# bankswitch-reg.net
KiCad netlist of a schematic drawn in EAGLE
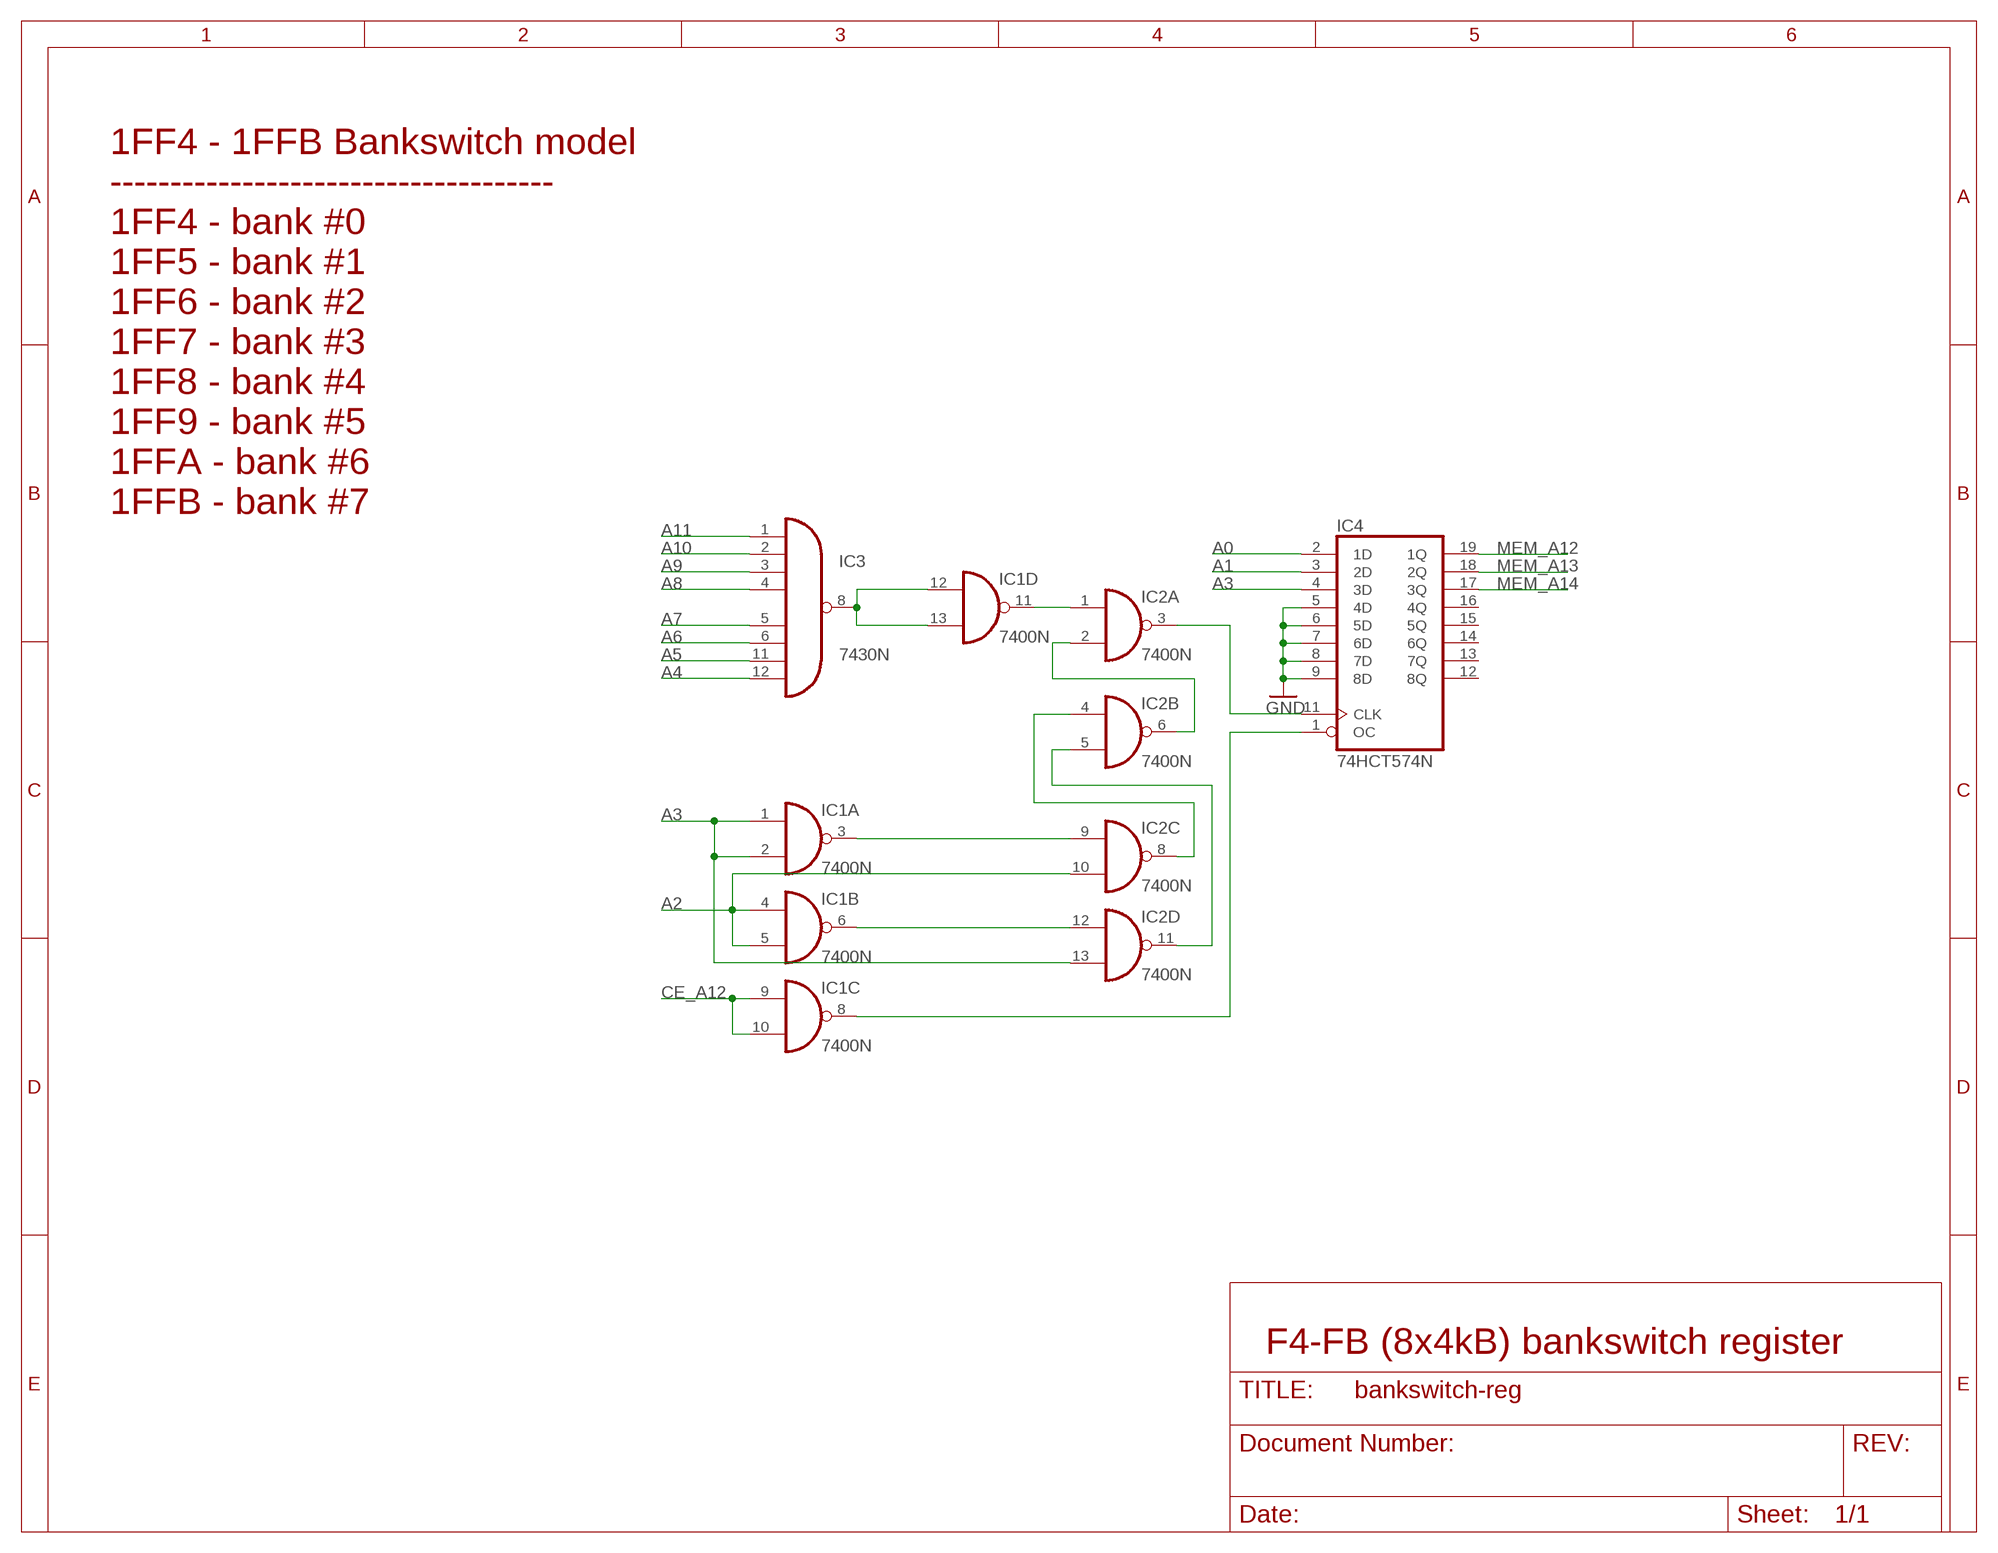
[diagram p0: schematic, sheet 1]

(export (version "E")
  (design (tool "Eeschema 10.0.6"))
  (components
    (comp (ref "IC1")
      (value "7400N")
      (footprint "eagle-import:DIL14")
      (libsource (lib "eagle-import") (part "7400N"))
    )
    (comp (ref "IC2")
      (value "7400N")
      (footprint "eagle-import:DIL14")
      (libsource (lib "eagle-import") (part "7400N"))
    )
    (comp (ref "IC3")
      (value "7430N")
      (footprint "eagle-import:DIL14")
      (libsource (lib "eagle-import") (part "7430N"))
    )
    (comp (ref "IC4")
      (value "74HCT574N")
      (footprint "eagle-import:DIL20")
      (libsource (lib "eagle-import") (part "74574NHCT"))
    )
  )
  (nets
    (net (code "1") (name "/A0") (class "Default")
      (node (ref "IC4") (pin "2") (pinfunction "1D_2") (pintype "input"))
    )
    (net (code "2") (name "/A1") (class "Default")
      (node (ref "IC4") (pin "3") (pinfunction "2D_3") (pintype "input"))
    )
    (net (code "3") (name "/A2") (class "Default")
      (node (ref "IC1") (pin "4") (pinfunction "I0_4") (pintype "input"))
      (node (ref "IC1") (pin "5") (pinfunction "I1_5") (pintype "input"))
      (node (ref "IC2") (pin "10") (pinfunction "I1_10") (pintype "input"))
    )
    (net (code "4") (name "/A3") (class "Default")
      (node (ref "IC1") (pin "1") (pinfunction "I0_1") (pintype "input"))
      (node (ref "IC1") (pin "2") (pinfunction "I1_2") (pintype "input"))
      (node (ref "IC2") (pin "13") (pinfunction "I1_13") (pintype "input"))
      (node (ref "IC4") (pin "4") (pinfunction "3D_4") (pintype "input"))
    )
    (net (code "5") (name "/A4") (class "Default")
      (node (ref "IC3") (pin "12") (pinfunction "I7_12") (pintype "input"))
    )
    (net (code "6") (name "/A5") (class "Default")
      (node (ref "IC3") (pin "11") (pinfunction "I6_11") (pintype "input"))
    )
    (net (code "7") (name "/A6") (class "Default")
      (node (ref "IC3") (pin "6") (pinfunction "I5_6") (pintype "input"))
    )
    (net (code "8") (name "/A7") (class "Default")
      (node (ref "IC3") (pin "5") (pinfunction "I4_5") (pintype "input"))
    )
    (net (code "9") (name "/A8") (class "Default")
      (node (ref "IC3") (pin "4") (pinfunction "I3_4") (pintype "input"))
    )
    (net (code "10") (name "/A9") (class "Default")
      (node (ref "IC3") (pin "3") (pinfunction "I2_3") (pintype "input"))
    )
    (net (code "11") (name "/A10") (class "Default")
      (node (ref "IC3") (pin "2") (pinfunction "I1_2") (pintype "input"))
    )
    (net (code "12") (name "/A11") (class "Default")
      (node (ref "IC3") (pin "1") (pinfunction "I0_1") (pintype "input"))
    )
    (net (code "13") (name "/CE_A12") (class "Default")
      (node (ref "IC1") (pin "10") (pinfunction "I1_10") (pintype "input"))
      (node (ref "IC1") (pin "9") (pinfunction "I0_9") (pintype "input"))
    )
    (net (code "14") (name "/MEM_A12") (class "Default")
      (node (ref "IC4") (pin "19") (pinfunction "1Q_19") (pintype "tri_state"))
    )
    (net (code "15") (name "/MEM_A13") (class "Default")
      (node (ref "IC4") (pin "18") (pinfunction "2Q_18") (pintype "tri_state"))
    )
    (net (code "16") (name "/MEM_A14") (class "Default")
      (node (ref "IC4") (pin "17") (pinfunction "3Q_17") (pintype "tri_state"))
    )
    (net (code "17") (name "GND") (class "Default")
      (node (ref "IC4") (pin "5") (pinfunction "4D_5") (pintype "input"))
      (node (ref "IC4") (pin "6") (pinfunction "5D_6") (pintype "input"))
      (node (ref "IC4") (pin "7") (pinfunction "6D_7") (pintype "input"))
      (node (ref "IC4") (pin "8") (pinfunction "7D_8") (pintype "input"))
      (node (ref "IC4") (pin "9") (pinfunction "8D_9") (pintype "input"))
    )
    (net (code "18") (name "Net-(IC1A-O)") (class "Default")
      (node (ref "IC1") (pin "3") (pinfunction "O_3") (pintype "output"))
      (node (ref "IC2") (pin "9") (pinfunction "I0_9") (pintype "input"))
    )
    (net (code "19") (name "Net-(IC1B-O)") (class "Default")
      (node (ref "IC1") (pin "6") (pinfunction "O_6") (pintype "output"))
      (node (ref "IC2") (pin "12") (pinfunction "I0_12") (pintype "input"))
    )
    (net (code "20") (name "Net-(IC1C-O)") (class "Default")
      (node (ref "IC1") (pin "8") (pinfunction "O_8") (pintype "output"))
      (node (ref "IC4") (pin "1") (pinfunction "OC_1") (pintype "input"))
    )
    (net (code "21") (name "Net-(IC1D-I0)") (class "Default")
      (node (ref "IC1") (pin "12") (pinfunction "I0_12") (pintype "input"))
      (node (ref "IC1") (pin "13") (pinfunction "I1_13") (pintype "input"))
      (node (ref "IC3") (pin "8") (pinfunction "O_8") (pintype "output"))
    )
    (net (code "22") (name "Net-(IC1D-O)") (class "Default")
      (node (ref "IC1") (pin "11") (pinfunction "O_11") (pintype "output"))
      (node (ref "IC2") (pin "1") (pinfunction "I0_1") (pintype "input"))
    )
    (net (code "23") (name "Net-(IC2A-I1)") (class "Default")
      (node (ref "IC2") (pin "2") (pinfunction "I1_2") (pintype "input"))
      (node (ref "IC2") (pin "6") (pinfunction "O_6") (pintype "output"))
    )
    (net (code "24") (name "Net-(IC2A-O)") (class "Default")
      (node (ref "IC2") (pin "3") (pinfunction "O_3") (pintype "output"))
      (node (ref "IC4") (pin "11") (pinfunction "CLK_11") (pintype "input"))
    )
    (net (code "25") (name "Net-(IC2B-I0)") (class "Default")
      (node (ref "IC2") (pin "4") (pinfunction "I0_4") (pintype "input"))
      (node (ref "IC2") (pin "8") (pinfunction "O_8") (pintype "output"))
    )
    (net (code "26") (name "Net-(IC2B-I1)") (class "Default")
      (node (ref "IC2") (pin "11") (pinfunction "O_11") (pintype "output"))
      (node (ref "IC2") (pin "5") (pinfunction "I1_5") (pintype "input"))
    )
    (net (code "27") (name "unconnected-(IC4A-4Q-Pad16)") (class "Default")
      (node (ref "IC4") (pin "16") (pinfunction "4Q_16") (pintype "tri_state"))
    )
    (net (code "28") (name "unconnected-(IC4A-5Q-Pad15)") (class "Default")
      (node (ref "IC4") (pin "15") (pinfunction "5Q_15") (pintype "tri_state"))
    )
    (net (code "29") (name "unconnected-(IC4A-6Q-Pad14)") (class "Default")
      (node (ref "IC4") (pin "14") (pinfunction "6Q_14") (pintype "tri_state"))
    )
    (net (code "30") (name "unconnected-(IC4A-7Q-Pad13)") (class "Default")
      (node (ref "IC4") (pin "13") (pinfunction "7Q_13") (pintype "tri_state"))
    )
    (net (code "31") (name "unconnected-(IC4A-8Q-Pad12)") (class "Default")
      (node (ref "IC4") (pin "12") (pinfunction "8Q_12") (pintype "tri_state"))
    )
  )
)
